# Temp_controlled_fan_2.net
KiCad netlist of a schematic drawn in EAGLE
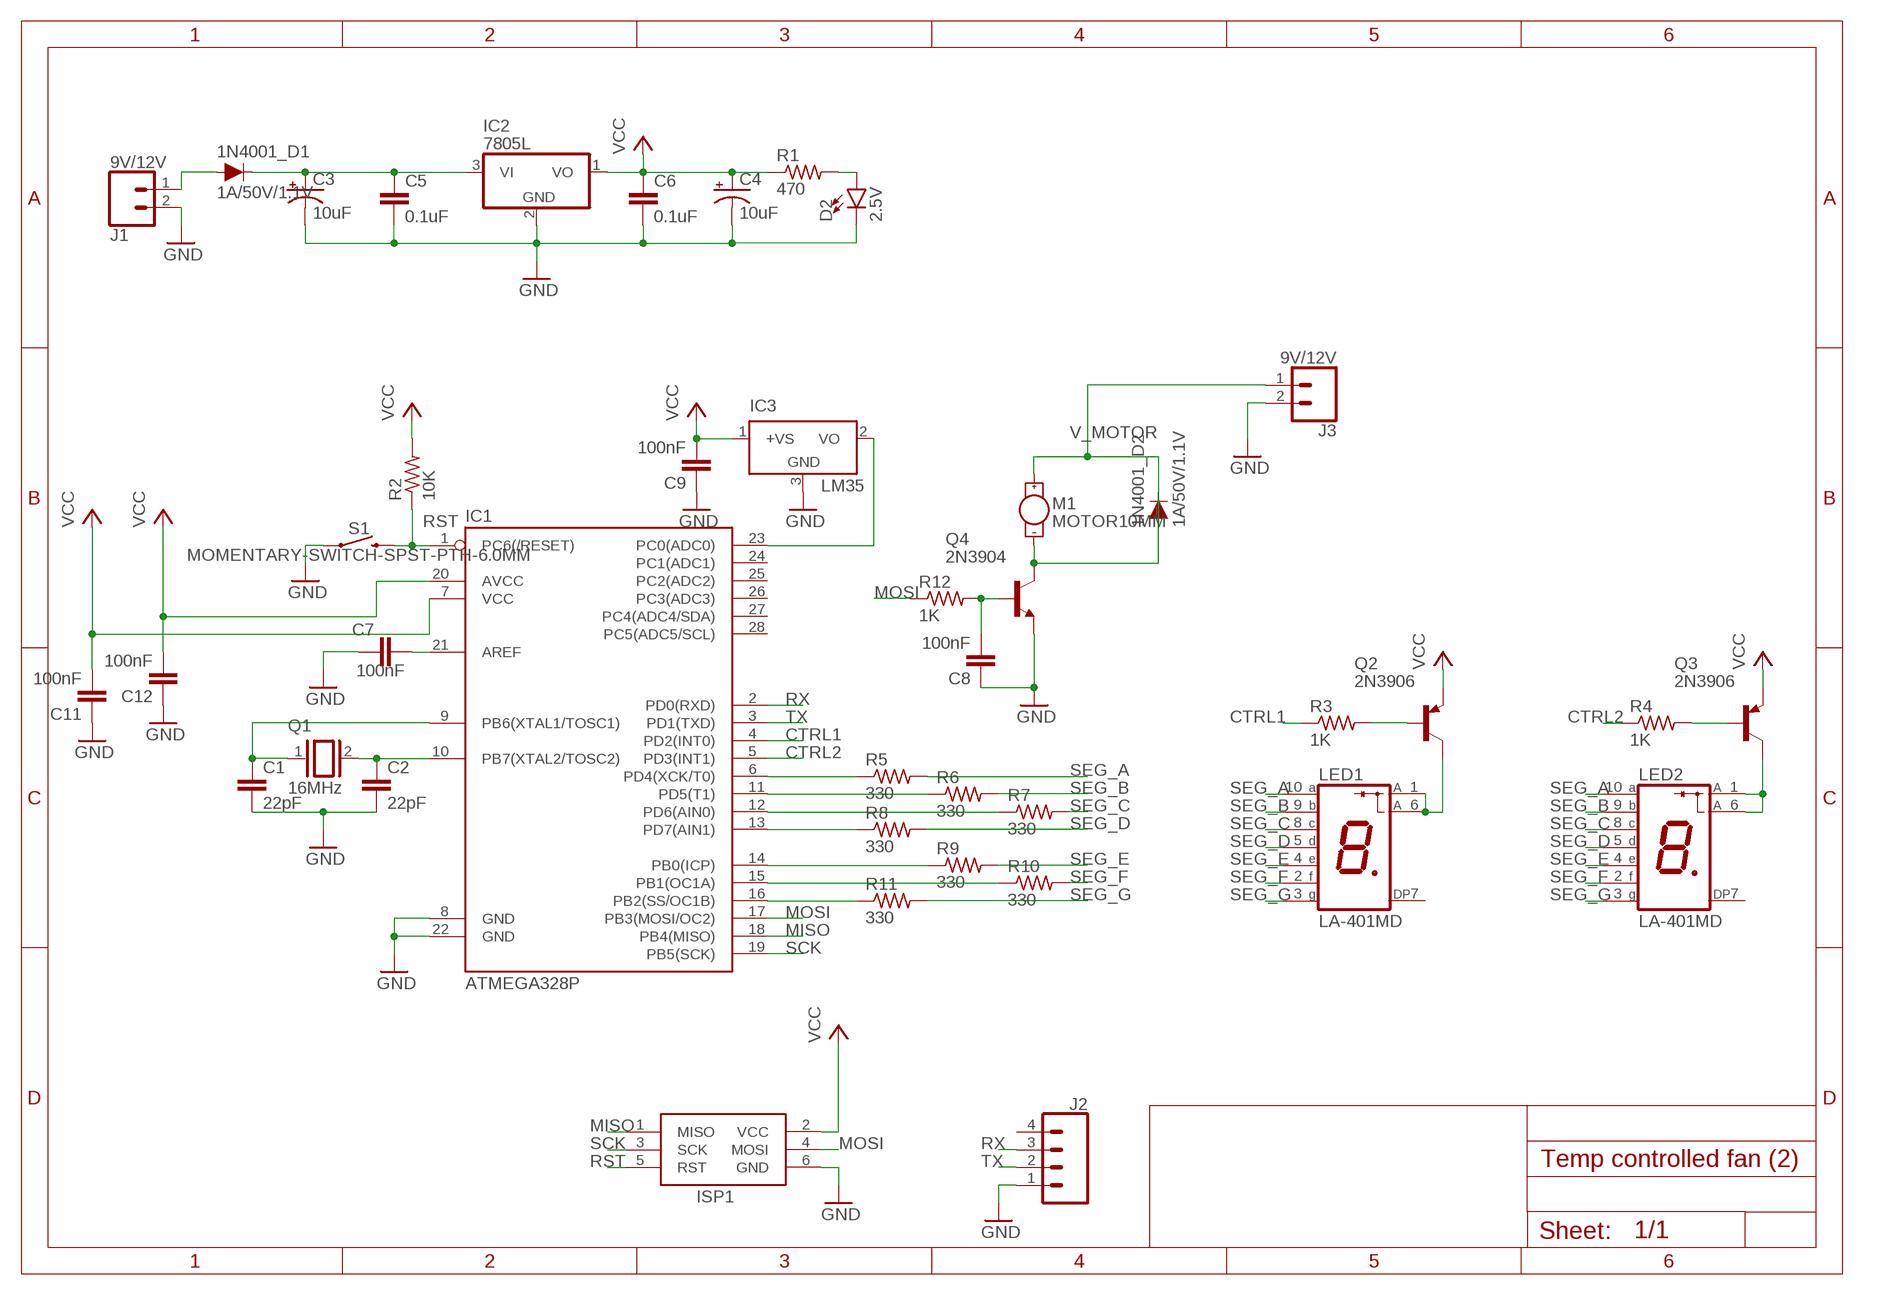
[diagram p0: schematic, sheet 1]

(export (version "E")
  (design (tool "Eeschema 10.0.6"))
  (components
    (comp (ref "1N4001_D1")
      (value "1A/50V/1.1V")
      (footprint "eagle-import:DIODE-1N4001")
      (libsource (lib "eagle-import") (part "DIODE-PTH"))
    )
    (comp (ref "1N4001_D2")
      (value "1A/50V/1.1V")
      (footprint "eagle-import:DIODE-1N4001")
      (libsource (lib "eagle-import") (part "DIODE-PTH"))
    )
    (comp (ref "C1")
      (value "22pF")
      (footprint "eagle-import:0603")
      (libsource (lib "eagle-import") (part "22PF-0603-50V-5%"))
    )
    (comp (ref "C2")
      (value "22pF")
      (footprint "eagle-import:0603")
      (libsource (lib "eagle-import") (part "22PF-0603-50V-5%"))
    )
    (comp (ref "C3")
      (value "10uF")
      (footprint "eagle-import:CPOL-RADIAL-2.5MM-5MM")
      (libsource (lib "eagle-import") (part "10UF-POLAR-RADIAL-2.5MM-25V-20%"))
    )
    (comp (ref "C4")
      (value "10uF")
      (footprint "eagle-import:CPOL-RADIAL-2.5MM-5MM")
      (libsource (lib "eagle-import") (part "10UF-POLAR-RADIAL-2.5MM-25V-20%"))
    )
    (comp (ref "C5")
      (value "0.1uF")
      (footprint "eagle-import:0603")
      (libsource (lib "eagle-import") (part "0.1UF-0603-25V-5%"))
    )
    (comp (ref "C6")
      (value "0.1uF")
      (footprint "eagle-import:0603")
      (libsource (lib "eagle-import") (part "0.1UF-0603-25V-5%"))
    )
    (comp (ref "C7")
      (value "100nF")
      (footprint "eagle-import:0603")
      (libsource (lib "eagle-import") (part "22PF-0603-50V-5%"))
    )
    (comp (ref "C8")
      (value "100nF")
      (footprint "eagle-import:0603")
      (libsource (lib "eagle-import") (part "22PF-0603-50V-5%"))
    )
    (comp (ref "C9")
      (value "100nF")
      (footprint "eagle-import:0603")
      (libsource (lib "eagle-import") (part "22PF-0603-50V-5%"))
    )
    (comp (ref "C11")
      (value "100nF")
      (footprint "eagle-import:0603")
      (libsource (lib "eagle-import") (part "22PF-0603-50V-5%"))
    )
    (comp (ref "C12")
      (value "100nF")
      (footprint "eagle-import:0603")
      (libsource (lib "eagle-import") (part "22PF-0603-50V-5%"))
    )
    (comp (ref "D2")
      (value "2.5V")
      (footprint "eagle-import:LED-1206")
      (libsource (lib "eagle-import") (part "LED1206"))
    )
    (comp (ref "IC1")
      (value "ATMEGA328P")
      (footprint "eagle-import:DIP28")
      (libsource (lib "eagle-import") (part "ATMEGA328P_PDIP"))
    )
    (comp (ref "IC2")
      (value "7805L")
      (footprint "eagle-import:TO92")
      (libsource (lib "eagle-import") (part "78L05"))
    )
    (comp (ref "IC3")
      (value "LM35")
      (footprint "eagle-import:TO92")
      (libsource (lib "eagle-import") (part "LM35CZ"))
    )
    (comp (ref "ISP1")
      (value "AVRISP-6")
      (footprint "eagle-import:AVRISP")
      (libsource (lib "eagle-import") (part "AVRISP-6"))
    )
    (comp (ref "J1")
      (value "9V/12V")
      (footprint "eagle-import:1X02_RA_PTH_FEMALE")
      (libsource (lib "eagle-import") (part "CONN_02PTH_RA_FEMALE"))
    )
    (comp (ref "J2")
      (value "CONN_04")
      (footprint "eagle-import:1X04")
      (libsource (lib "eagle-import") (part "CONN_04"))
    )
    (comp (ref "J3")
      (value "9V/12V")
      (footprint "eagle-import:1X02_RA_PTH_FEMALE")
      (libsource (lib "eagle-import") (part "CONN_02PTH_RA_FEMALE"))
    )
    (comp (ref "LED1")
      (value "LA-401MD")
      (footprint "eagle-import:LA-401")
      (libsource (lib "eagle-import") (part "LA-401DM"))
    )
    (comp (ref "LED2")
      (value "LA-401MD")
      (footprint "eagle-import:LA-401")
      (libsource (lib "eagle-import") (part "LA-401DM"))
    )
    (comp (ref "M1")
      (value "MOTOR10MM")
      (footprint "eagle-import:VIBE-MOTOR-10MM")
      (libsource (lib "eagle-import") (part "MOTOR10MM"))
    )
    (comp (ref "Q1")
      (value "16MHz")
      (footprint "eagle-import:QS")
      (libsource (lib "eagle-import") (part "XTAL/S"))
    )
    (comp (ref "Q2")
      (value "2N3906")
      (footprint "eagle-import:TO92")
      (libsource (lib "eagle-import") (part "2N3906"))
    )
    (comp (ref "Q3")
      (value "2N3906")
      (footprint "eagle-import:TO92")
      (libsource (lib "eagle-import") (part "2N3906"))
    )
    (comp (ref "Q4")
      (value "2N3904")
      (footprint "eagle-import:TO92")
      (libsource (lib "eagle-import") (part "2N3904"))
    )
    (comp (ref "R1")
      (value "470")
      (footprint "eagle-import:R0805")
      (libsource (lib "eagle-import") (part "R-US_R0805"))
    )
    (comp (ref "R2")
      (value "10K")
      (footprint "eagle-import:R0805")
      (libsource (lib "eagle-import") (part "R-US_R0805"))
    )
    (comp (ref "R3")
      (value "1K")
      (footprint "eagle-import:R0805")
      (libsource (lib "eagle-import") (part "R-US_R0805"))
    )
    (comp (ref "R4")
      (value "1K")
      (footprint "eagle-import:R0805")
      (libsource (lib "eagle-import") (part "R-US_R0805"))
    )
    (comp (ref "R5")
      (value "330")
      (footprint "eagle-import:R0805")
      (libsource (lib "eagle-import") (part "R-US_R0805"))
    )
    (comp (ref "R6")
      (value "330")
      (footprint "eagle-import:R0805")
      (libsource (lib "eagle-import") (part "R-US_R0805"))
    )
    (comp (ref "R7")
      (value "330")
      (footprint "eagle-import:R0805")
      (libsource (lib "eagle-import") (part "R-US_R0805"))
    )
    (comp (ref "R8")
      (value "330")
      (footprint "eagle-import:R0805")
      (libsource (lib "eagle-import") (part "R-US_R0805"))
    )
    (comp (ref "R9")
      (value "330")
      (footprint "eagle-import:R0805")
      (libsource (lib "eagle-import") (part "R-US_R0805"))
    )
    (comp (ref "R10")
      (value "330")
      (footprint "eagle-import:R0805")
      (libsource (lib "eagle-import") (part "R-US_R0805"))
    )
    (comp (ref "R11")
      (value "330")
      (footprint "eagle-import:R0805")
      (libsource (lib "eagle-import") (part "R-US_R0805"))
    )
    (comp (ref "R12")
      (value "1K")
      (footprint "eagle-import:R0805")
      (libsource (lib "eagle-import") (part "R-US_R0805"))
    )
    (comp (ref "S1")
      (value "MOMENTARY-SWITCH-SPST-PTH-6.0MM")
      (footprint "eagle-import:TACTILE_SWITCH_PTH_6.0MM")
      (libsource (lib "eagle-import") (part "MOMENTARY-SWITCH-SPST-PTH-6.0MM"))
    )
  )
  (nets
    (net (code "1") (name "/CTRL1") (class "Default")
      (node (ref "IC1") (pin "4") (pinfunction "PD2(INT0)_4") (pintype "bidirectional"))
      (node (ref "R3") (pin "1") (pinfunction "1_1") (pintype "passive"))
    )
    (net (code "2") (name "/CTRL2") (class "Default")
      (node (ref "IC1") (pin "5") (pinfunction "PD3(INT1)_5") (pintype "bidirectional"))
      (node (ref "R4") (pin "1") (pinfunction "1_1") (pintype "passive"))
    )
    (net (code "3") (name "/MISO") (class "Default")
      (node (ref "IC1") (pin "18") (pinfunction "PB4(MISO)_18") (pintype "bidirectional"))
      (node (ref "ISP1") (pin "1") (pinfunction "MISO_1") (pintype "input"))
    )
    (net (code "4") (name "/MOSI") (class "Default")
      (node (ref "IC1") (pin "17") (pinfunction "PB3(MOSI/OC2)_17") (pintype "bidirectional"))
      (node (ref "ISP1") (pin "4") (pinfunction "MOSI_4") (pintype "output"))
      (node (ref "R12") (pin "1") (pinfunction "1_1") (pintype "passive"))
    )
    (net (code "5") (name "/RST") (class "Default")
      (node (ref "IC1") (pin "1") (pinfunction "PC6(/RESET)_1") (pintype "bidirectional"))
      (node (ref "ISP1") (pin "5") (pinfunction "RST_5") (pintype "output"))
      (node (ref "R2") (pin "1") (pinfunction "1_1") (pintype "passive"))
      (node (ref "S1") (pin "3") (pinfunction "2_3") (pintype "passive"))
    )
    (net (code "6") (name "/RX") (class "Default")
      (node (ref "IC1") (pin "2") (pinfunction "PD0(RXD)_2") (pintype "bidirectional"))
      (node (ref "J2") (pin "3") (pinfunction "3_3") (pintype "passive"))
    )
    (net (code "7") (name "/SCK") (class "Default")
      (node (ref "IC1") (pin "19") (pinfunction "PB5(SCK)_19") (pintype "bidirectional"))
      (node (ref "ISP1") (pin "3") (pinfunction "SCK_3") (pintype "output"))
    )
    (net (code "8") (name "/SEG_A") (class "Default")
      (node (ref "LED1") (pin "10") (pinfunction "A_10") (pintype "passive"))
      (node (ref "LED2") (pin "10") (pinfunction "A_10") (pintype "passive"))
      (node (ref "R5") (pin "2") (pinfunction "2_2") (pintype "passive"))
    )
    (net (code "9") (name "/SEG_B") (class "Default")
      (node (ref "LED1") (pin "9") (pinfunction "B_9") (pintype "passive"))
      (node (ref "LED2") (pin "9") (pinfunction "B_9") (pintype "passive"))
      (node (ref "R6") (pin "2") (pinfunction "2_2") (pintype "passive"))
    )
    (net (code "10") (name "/SEG_C") (class "Default")
      (node (ref "LED1") (pin "8") (pinfunction "C_8") (pintype "passive"))
      (node (ref "LED2") (pin "8") (pinfunction "C_8") (pintype "passive"))
      (node (ref "R7") (pin "2") (pinfunction "2_2") (pintype "passive"))
    )
    (net (code "11") (name "/SEG_D") (class "Default")
      (node (ref "LED1") (pin "5") (pinfunction "D_5") (pintype "passive"))
      (node (ref "LED2") (pin "5") (pinfunction "D_5") (pintype "passive"))
      (node (ref "R8") (pin "2") (pinfunction "2_2") (pintype "passive"))
    )
    (net (code "12") (name "/SEG_E") (class "Default")
      (node (ref "LED1") (pin "4") (pinfunction "E_4") (pintype "passive"))
      (node (ref "LED2") (pin "4") (pinfunction "E_4") (pintype "passive"))
      (node (ref "R9") (pin "2") (pinfunction "2_2") (pintype "passive"))
    )
    (net (code "13") (name "/SEG_F") (class "Default")
      (node (ref "LED1") (pin "2") (pinfunction "F_2") (pintype "passive"))
      (node (ref "LED2") (pin "2") (pinfunction "F_2") (pintype "passive"))
      (node (ref "R10") (pin "2") (pinfunction "2_2") (pintype "passive"))
    )
    (net (code "14") (name "/SEG_G") (class "Default")
      (node (ref "LED1") (pin "3") (pinfunction "G_3") (pintype "passive"))
      (node (ref "LED2") (pin "3") (pinfunction "G_3") (pintype "passive"))
      (node (ref "R11") (pin "2") (pinfunction "2_2") (pintype "passive"))
    )
    (net (code "15") (name "/TX") (class "Default")
      (node (ref "IC1") (pin "3") (pinfunction "PD1(TXD)_3") (pintype "bidirectional"))
      (node (ref "J2") (pin "2") (pinfunction "2_2") (pintype "passive"))
    )
    (net (code "16") (name "/V_MOTOR") (class "Default")
      (node (ref "1N4001_D2") (pin "A") (pinfunction "A_A") (pintype "passive"))
      (node (ref "J3") (pin "1") (pinfunction "1_1") (pintype "passive"))
      (node (ref "M1") (pin "+") (pinfunction "+_+") (pintype "bidirectional"))
    )
    (net (code "17") (name "GND") (class "Default")
      (node (ref "C1") (pin "2") (pinfunction "2_2") (pintype "passive"))
      (node (ref "C11") (pin "1") (pinfunction "1_1") (pintype "passive"))
      (node (ref "C12") (pin "1") (pinfunction "1_1") (pintype "passive"))
      (node (ref "C2") (pin "2") (pinfunction "2_2") (pintype "passive"))
      (node (ref "C3") (pin "2") (pinfunction "-_2") (pintype "passive"))
      (node (ref "C4") (pin "2") (pinfunction "-_2") (pintype "passive"))
      (node (ref "C5") (pin "2") (pinfunction "2_2") (pintype "passive"))
      (node (ref "C6") (pin "2") (pinfunction "2_2") (pintype "passive"))
      (node (ref "C7") (pin "1") (pinfunction "1_1") (pintype "passive"))
      (node (ref "C8") (pin "1") (pinfunction "1_1") (pintype "passive"))
      (node (ref "C9") (pin "1") (pinfunction "1_1") (pintype "passive"))
      (node (ref "D2") (pin "C") (pinfunction "C_C") (pintype "passive"))
      (node (ref "IC1") (pin "22") (pinfunction "GND_22") (pintype "bidirectional"))
      (node (ref "IC1") (pin "8") (pinfunction "GND_8") (pintype "bidirectional"))
      (node (ref "IC2") (pin "2") (pinfunction "GND_2") (pintype "passive"))
      (node (ref "IC3") (pin "3") (pinfunction "GND_3") (pintype "power_in"))
      (node (ref "ISP1") (pin "6") (pinfunction "GND_6") (pintype "power_in"))
      (node (ref "J1") (pin "2") (pinfunction "2_2") (pintype "passive"))
      (node (ref "J2") (pin "1") (pinfunction "1_1") (pintype "passive"))
      (node (ref "J3") (pin "2") (pinfunction "2_2") (pintype "passive"))
      (node (ref "Q4") (pin "3") (pinfunction "E_3") (pintype "passive"))
      (node (ref "S1") (pin "1") (pinfunction "1_1") (pintype "passive"))
    )
    (net (code "18") (name "Net-(1N4001_D1-PadA)") (class "Default")
      (node (ref "1N4001_D1") (pin "A") (pinfunction "A_A") (pintype "passive"))
      (node (ref "J1") (pin "1") (pinfunction "1_1") (pintype "passive"))
    )
    (net (code "19") (name "Net-(C3-+)") (class "Default")
      (node (ref "1N4001_D1") (pin "C") (pinfunction "C_C") (pintype "passive"))
      (node (ref "C3") (pin "1") (pinfunction "+_1") (pintype "passive"))
      (node (ref "C5") (pin "1") (pinfunction "1_1") (pintype "passive"))
      (node (ref "IC2") (pin "3") (pinfunction "VI_3") (pintype "input"))
    )
    (net (code "20") (name "Net-(D2-PadA)") (class "Default")
      (node (ref "D2") (pin "A") (pinfunction "A_A") (pintype "passive"))
      (node (ref "R1") (pin "2") (pinfunction "2_2") (pintype "passive"))
    )
    (net (code "21") (name "Net-(IC1-AREF)") (class "Default")
      (node (ref "C7") (pin "2") (pinfunction "2_2") (pintype "passive"))
      (node (ref "IC1") (pin "21") (pinfunction "AREF_21") (pintype "bidirectional"))
    )
    (net (code "22") (name "Net-(IC1-PB0(ICP))") (class "Default")
      (node (ref "IC1") (pin "14") (pinfunction "PB0(ICP)_14") (pintype "bidirectional"))
      (node (ref "R9") (pin "1") (pinfunction "1_1") (pintype "passive"))
    )
    (net (code "23") (name "Net-(IC1-PB1(OC1A))") (class "Default")
      (node (ref "IC1") (pin "15") (pinfunction "PB1(OC1A)_15") (pintype "bidirectional"))
      (node (ref "R10") (pin "1") (pinfunction "1_1") (pintype "passive"))
    )
    (net (code "24") (name "Net-(IC1-PB2(SS{slash}OC1B))") (class "Default")
      (node (ref "IC1") (pin "16") (pinfunction "PB2(SS/OC1B)_16") (pintype "bidirectional"))
      (node (ref "R11") (pin "1") (pinfunction "1_1") (pintype "passive"))
    )
    (net (code "25") (name "Net-(IC1-PB6(XTAL1{slash}TOSC1))") (class "Default")
      (node (ref "C1") (pin "1") (pinfunction "1_1") (pintype "passive"))
      (node (ref "IC1") (pin "9") (pinfunction "PB6(XTAL1/TOSC1)_9") (pintype "bidirectional"))
      (node (ref "Q1") (pin "1") (pinfunction "1_1") (pintype "passive"))
    )
    (net (code "26") (name "Net-(IC1-PB7(XTAL2{slash}TOSC2))") (class "Default")
      (node (ref "C2") (pin "1") (pinfunction "1_1") (pintype "passive"))
      (node (ref "IC1") (pin "10") (pinfunction "PB7(XTAL2/TOSC2)_10") (pintype "bidirectional"))
      (node (ref "Q1") (pin "2") (pinfunction "2_2") (pintype "passive"))
    )
    (net (code "27") (name "Net-(IC1-PC0(ADC0))") (class "Default")
      (node (ref "IC1") (pin "23") (pinfunction "PC0(ADC0)_23") (pintype "bidirectional"))
      (node (ref "IC3") (pin "2") (pinfunction "VO_2") (pintype "input"))
    )
    (net (code "28") (name "Net-(IC1-PD4(XCK{slash}T0))") (class "Default")
      (node (ref "IC1") (pin "6") (pinfunction "PD4(XCK/T0)_6") (pintype "bidirectional"))
      (node (ref "R5") (pin "1") (pinfunction "1_1") (pintype "passive"))
    )
    (net (code "29") (name "Net-(IC1-PD5(T1))") (class "Default")
      (node (ref "IC1") (pin "11") (pinfunction "PD5(T1)_11") (pintype "bidirectional"))
      (node (ref "R6") (pin "1") (pinfunction "1_1") (pintype "passive"))
    )
    (net (code "30") (name "Net-(IC1-PD6(AIN0))") (class "Default")
      (node (ref "IC1") (pin "12") (pinfunction "PD6(AIN0)_12") (pintype "bidirectional"))
      (node (ref "R7") (pin "1") (pinfunction "1_1") (pintype "passive"))
    )
    (net (code "31") (name "Net-(IC1-PD7(AIN1))") (class "Default")
      (node (ref "IC1") (pin "13") (pinfunction "PD7(AIN1)_13") (pintype "bidirectional"))
      (node (ref "R8") (pin "1") (pinfunction "1_1") (pintype "passive"))
    )
    (net (code "32") (name "Net-(Q2-B)") (class "Default")
      (node (ref "Q2") (pin "2") (pinfunction "B_2") (pintype "passive"))
      (node (ref "R3") (pin "2") (pinfunction "2_2") (pintype "passive"))
    )
    (net (code "33") (name "Net-(Q2-C)") (class "Default")
      (node (ref "LED1") (pin "1") (pinfunction "A_1") (pintype "passive"))
      (node (ref "LED1") (pin "6") (pinfunction "A_6") (pintype "passive"))
      (node (ref "Q2") (pin "1") (pinfunction "C_1") (pintype "passive"))
    )
    (net (code "34") (name "Net-(Q3-B)") (class "Default")
      (node (ref "Q3") (pin "2") (pinfunction "B_2") (pintype "passive"))
      (node (ref "R4") (pin "2") (pinfunction "2_2") (pintype "passive"))
    )
    (net (code "35") (name "Net-(Q3-C)") (class "Default")
      (node (ref "LED2") (pin "1") (pinfunction "A_1") (pintype "passive"))
      (node (ref "LED2") (pin "6") (pinfunction "A_6") (pintype "passive"))
      (node (ref "Q3") (pin "1") (pinfunction "C_1") (pintype "passive"))
    )
    (net (code "36") (name "Net-(Q4-B)") (class "Default")
      (node (ref "C8") (pin "2") (pinfunction "2_2") (pintype "passive"))
      (node (ref "Q4") (pin "2") (pinfunction "B_2") (pintype "passive"))
      (node (ref "R12") (pin "2") (pinfunction "2_2") (pintype "passive"))
    )
    (net (code "37") (name "Net-(Q4-C)") (class "Default")
      (node (ref "1N4001_D2") (pin "C") (pinfunction "C_C") (pintype "passive"))
      (node (ref "M1") (pin "-") (pinfunction "-_-") (pintype "bidirectional"))
      (node (ref "Q4") (pin "1") (pinfunction "C_1") (pintype "passive"))
    )
    (net (code "38") (name "VCC") (class "Default")
      (node (ref "C11") (pin "2") (pinfunction "2_2") (pintype "passive"))
      (node (ref "C12") (pin "2") (pinfunction "2_2") (pintype "passive"))
      (node (ref "C4") (pin "1") (pinfunction "+_1") (pintype "passive"))
      (node (ref "C6") (pin "1") (pinfunction "1_1") (pintype "passive"))
      (node (ref "C9") (pin "2") (pinfunction "2_2") (pintype "passive"))
      (node (ref "IC1") (pin "20") (pinfunction "AVCC_20") (pintype "bidirectional"))
      (node (ref "IC1") (pin "7") (pinfunction "VCC_7") (pintype "bidirectional"))
      (node (ref "IC2") (pin "1") (pinfunction "VO_1") (pintype "passive"))
      (node (ref "IC3") (pin "1") (pinfunction "+VS_1") (pintype "input"))
      (node (ref "ISP1") (pin "2") (pinfunction "VCC_2") (pintype "power_in"))
      (node (ref "Q2") (pin "3") (pinfunction "E_3") (pintype "passive"))
      (node (ref "Q3") (pin "3") (pinfunction "E_3") (pintype "passive"))
      (node (ref "R1") (pin "1") (pinfunction "1_1") (pintype "passive"))
      (node (ref "R2") (pin "2") (pinfunction "2_2") (pintype "passive"))
    )
    (net (code "39") (name "unconnected-(IC1-PC1(ADC1)-Pad24)") (class "Default")
      (node (ref "IC1") (pin "24") (pinfunction "PC1(ADC1)_24") (pintype "bidirectional"))
    )
    (net (code "40") (name "unconnected-(IC1-PC2(ADC2)-Pad25)") (class "Default")
      (node (ref "IC1") (pin "25") (pinfunction "PC2(ADC2)_25") (pintype "bidirectional"))
    )
    (net (code "41") (name "unconnected-(IC1-PC3(ADC3)-Pad26)") (class "Default")
      (node (ref "IC1") (pin "26") (pinfunction "PC3(ADC3)_26") (pintype "bidirectional"))
    )
    (net (code "42") (name "unconnected-(IC1-PC4(ADC4{slash}SDA)-Pad27)") (class "Default")
      (node (ref "IC1") (pin "27") (pinfunction "PC4(ADC4/SDA)_27") (pintype "bidirectional"))
    )
    (net (code "43") (name "unconnected-(IC1-PC5(ADC5{slash}SCL)-Pad28)") (class "Default")
      (node (ref "IC1") (pin "28") (pinfunction "PC5(ADC5/SCL)_28") (pintype "bidirectional"))
    )
    (net (code "44") (name "unconnected-(J2-Pad4)") (class "Default")
      (node (ref "J2") (pin "4") (pinfunction "4_4") (pintype "passive"))
    )
    (net (code "45") (name "unconnected-(LED1-DP-Pad7)") (class "Default")
      (node (ref "LED1") (pin "7") (pinfunction "DP_7") (pintype "passive"))
    )
    (net (code "46") (name "unconnected-(LED2-DP-Pad7)") (class "Default")
      (node (ref "LED2") (pin "7") (pinfunction "DP_7") (pintype "passive"))
    )
  )
)
